# 03-GPS.net
KiCad netlist of a schematic drawn in Altium Designer
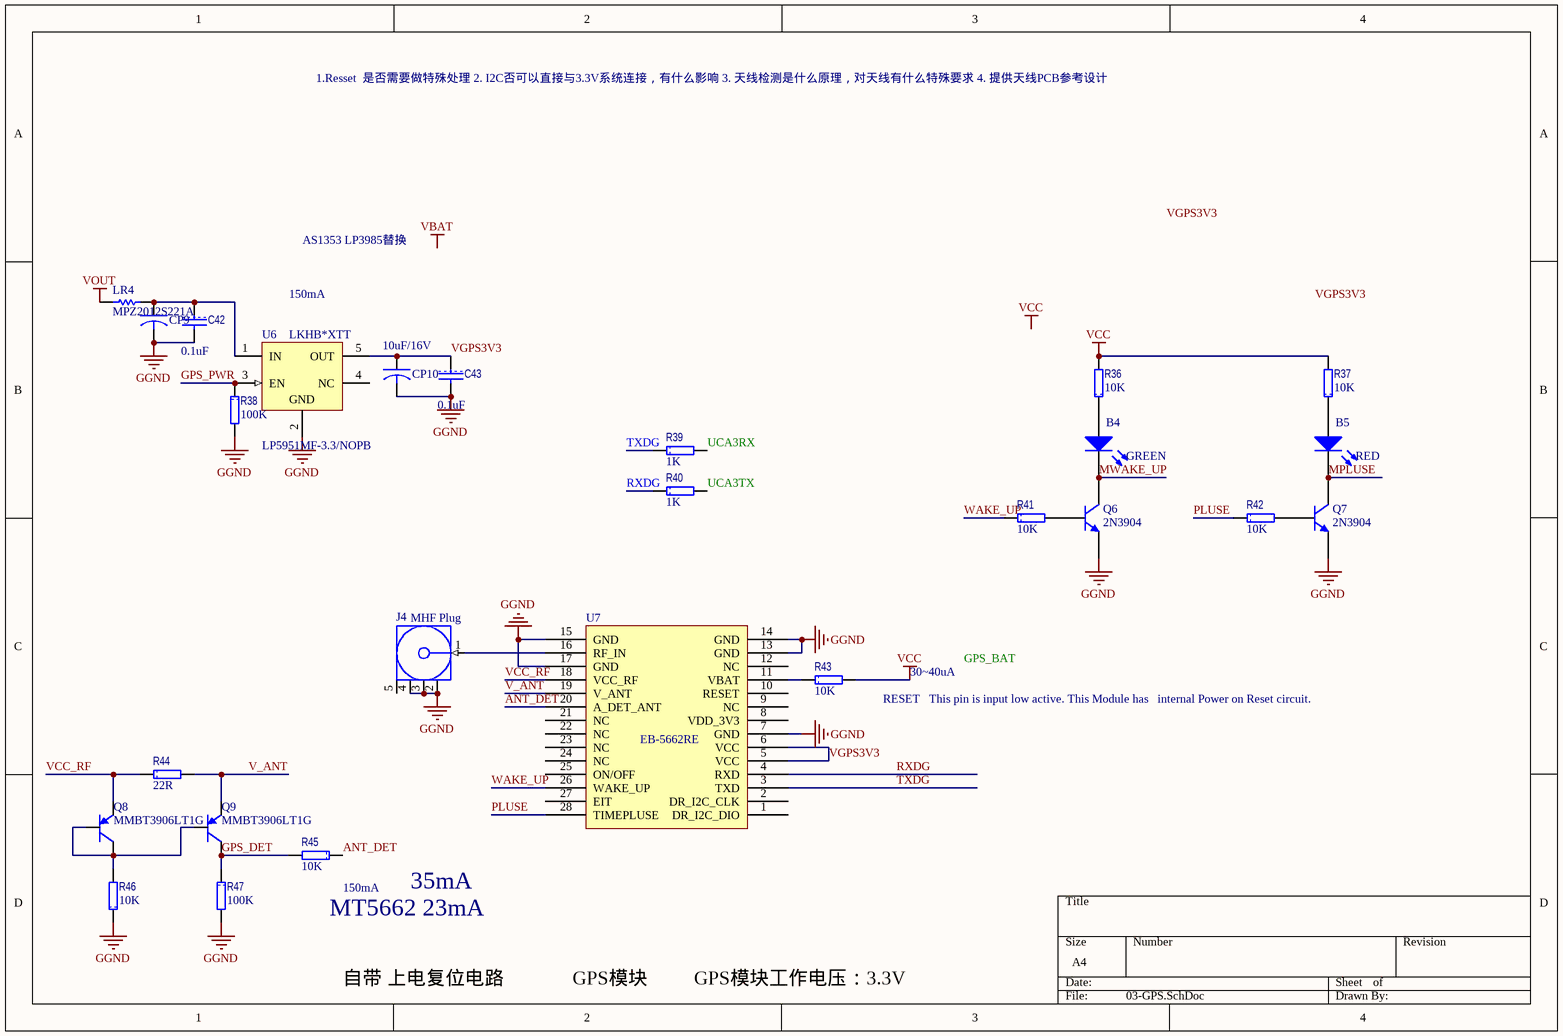
[diagram p0: 03-GPS.SchDoc]

(export (version "E")
  (design (tool "Eeschema 10.0.6"))
  (components
    (comp (ref "B4")
      (value "GREEN")
      (footprint "0805LED")
      (description "Typical RED, GREEN, YELLOW, AMBER GaAs LED")
      (fields (field (name "PUBLISHER") "Altium Limited"))
      (libsource (lib "Miscellaneous Devices") (part "LED2"))
    )
    (comp (ref "B5")
      (value "RED")
      (footprint "0805LED")
      (description "Typical RED, GREEN, YELLOW, AMBER GaAs LED")
      (fields (field (name "PUBLISHER") "Altium Limited"))
      (libsource (lib "Miscellaneous Devices") (part "LED2"))
    )
    (comp (ref "C42")
      (value "0.1uF")
      (footprint "1608[0603]C")
      (description "多层陶瓷电容器MLCC - SMD/SMT 0603 0.1uF 50volts X7R 10%")
      (fields (field (name "MANUFACTURER") "TDK") (field (name "MANUFACTURER PART NUMBER") "C1608X7R1H104K"))
      (libsource (lib "*") (part "CAP"))
    )
    (comp (ref "C43")
      (value "0.1uF")
      (footprint "1608[0603]C")
      (description "多层陶瓷电容器MLCC - SMD/SMT 0603 0.1uF 50volts X7R 10%")
      (fields (field (name "MANUFACTURER") "TDK") (field (name "MANUFACTURER PART NUMBER") "C1608X7R1H104K"))
      (libsource (lib "*") (part "CAP"))
    )
    (comp (ref "CP9")
      (value "TAJA106K016RNJ")
      (footprint "3216[1206]CB")
      (description "钽质电容器-固体SMD 16volts 10uF 10%")
      (fields (field (name "MANUFACTURER") "AVX"))
      (libsource (lib "*") (part "CAPACITOR"))
    )
    (comp (ref "CP10")
      (value "10uF/16V")
      (footprint "3216[1206]CB")
      (description "钽质电容器-固体SMD 16volts 10uF 10%")
      (fields (field (name "MANUFACTURER") "AVX") (field (name "MANUFACTURER PART NUMBER") "TAJA106K016RNJ"))
      (libsource (lib "*") (part "CAPACITOR"))
    )
    (comp (ref "J4")
      (value "MHF Plug")
      (footprint "MHF[MCB3]-V4")
      (description "插针 RF 连接器 ONBRD IPEX MHF RECEPTACLE")
      (fields
        (field (name "MANUFACTURER") "Taoglas")
        (field (name "MANUFACTURER PART NUMBER") "RECE-20279-001E-01")
      )
      (libsource (lib "Miscellaneous Connectors") (part "COAX-F"))
    )
    (comp (ref "LR4")
      (value "MPZ2012S221A")
      (footprint "2012[0805]")
      (description "电磁干扰滤波珠子、扼流圈和阵列 Ferrite Chip Beads")
      (fields (field (name "MANUFACTURER") "TDK"))
      (libsource (lib "Miscellaneous Devices") (part "Res Semi"))
    )
    (comp (ref "Q6")
      (value "2N3904")
      (footprint "SOT23_N")
      (description "NPN General Purpose Amplifier")
      (fields (field (name "PUBLISHER") "Altium Limited"))
      (libsource (lib "Miscellaneous Devices") (part "2N3904"))
    )
    (comp (ref "Q7")
      (value "2N3904")
      (footprint "SOT23_N")
      (description "NPN General Purpose Amplifier")
      (fields (field (name "PUBLISHER") "Altium Limited"))
      (libsource (lib "Miscellaneous Devices") (part "2N3904"))
    )
    (comp (ref "Q8")
      (value "MMBT3906LT1G")
      (footprint "SOT23_N")
      (description "两极晶体管 - BJT 200mA 40V PNP")
      (fields (field (name "MANUFACTURER") "ON Semiconductor"))
      (libsource (lib "*") (part "MMBT3096"))
    )
    (comp (ref "Q9")
      (value "MMBT3906LT1G")
      (footprint "SOT23_N")
      (description "两极晶体管 - BJT 200mA 40V PNP")
      (fields (field (name "MANUFACTURER") "ON Semiconductor"))
      (libsource (lib "*") (part "MMBT3096"))
    )
    (comp (ref "R36")
      (value "10K")
      (footprint "1608[0603]R")
      (description "厚膜电阻器 - SMD 1/10watt 10Kohms 1%")
      (fields
        (field (name "MANUFACTURER") "Vishay / Dale")
        (field (name "MANUFACTURER PART NUMBER") "CRCW060310K0FKEA")
      )
      (libsource (lib "10K 1%") (part "RES"))
    )
    (comp (ref "R37")
      (value "10K")
      (footprint "1608[0603]R")
      (description "厚膜电阻器 - SMD 1/10watt 10Kohms 1%")
      (fields
        (field (name "MANUFACTURER") "Vishay / Dale")
        (field (name "MANUFACTURER PART NUMBER") "CRCW060310K0FKEA")
      )
      (libsource (lib "10K 1%") (part "RES"))
    )
    (comp (ref "R38")
      (value "100K")
      (footprint "1608[0603]R")
      (description "厚膜电阻器 - SMD 1/10watt 100Kohms 1%")
      (fields
        (field (name "MANUFACTURER") "Vishay / Dale")
        (field (name "MANUFACTURER PART NUMBER") "CRCW0603100KFKEA")
      )
      (libsource (lib "100K 1%") (part "RES"))
    )
    (comp (ref "R39")
      (value "1K")
      (footprint "1608[0603]R")
      (description "厚膜电阻器 - SMD 1/10watt 1.0Kohms 1%")
      (fields
        (field (name "MANUFACTURER") "Vishay / Dale")
        (field (name "MANUFACTURER PART NUMBER") "CRCW06031K00FKEA")
      )
      (libsource (lib "1K 1%") (part "RES"))
    )
    (comp (ref "R40")
      (value "1K")
      (footprint "1608[0603]R")
      (description "厚膜电阻器 - SMD 1/10watt 1.0Kohms 1%")
      (fields
        (field (name "MANUFACTURER") "Vishay / Dale")
        (field (name "MANUFACTURER PART NUMBER") "CRCW06031K00FKEA")
      )
      (libsource (lib "1K 1%") (part "RES"))
    )
    (comp (ref "R41")
      (value "10K")
      (footprint "1608[0603]R")
      (description "厚膜电阻器 - SMD 1/10watt 10Kohms 1%")
      (fields
        (field (name "MANUFACTURER") "Vishay / Dale")
        (field (name "MANUFACTURER PART NUMBER") "CRCW060310K0FKEA")
      )
      (libsource (lib "10K 1%") (part "RES"))
    )
    (comp (ref "R42")
      (value "10K")
      (footprint "1608[0603]R")
      (description "厚膜电阻器 - SMD 1/10watt 10Kohms 1%")
      (fields
        (field (name "MANUFACTURER") "Vishay / Dale")
        (field (name "MANUFACTURER PART NUMBER") "CRCW060310K0FKEA")
      )
      (libsource (lib "10K 1%") (part "RES"))
    )
    (comp (ref "R43")
      (value "10K")
      (footprint "1608[0603]R")
      (description "厚膜电阻器 - SMD 1/10watt 10Kohms 1%")
      (fields
        (field (name "MANUFACTURER") "Vishay / Dale")
        (field (name "MANUFACTURER PART NUMBER") "CRCW060310K0FKEA")
      )
      (libsource (lib "10K 1%") (part "RES"))
    )
    (comp (ref "R44")
      (value "22R")
      (footprint "1608[0603]R")
      (description "厚膜电阻器 - SMD 1/10watt 22ohms 1%")
      (fields
        (field (name "MANUFACTURER") "Vishay / Dale")
        (field (name "MANUFACTURER PART NUMBER") "CRCW060322R0FKEA")
      )
      (libsource (lib "22R 1%") (part "RES"))
    )
    (comp (ref "R45")
      (value "10K")
      (footprint "1608[0603]R")
      (description "厚膜电阻器 - SMD 1/10watt 10Kohms 1%")
      (fields
        (field (name "MANUFACTURER") "Vishay / Dale")
        (field (name "MANUFACTURER PART NUMBER") "CRCW060310K0FKEA")
      )
      (libsource (lib "10K 1%") (part "RES"))
    )
    (comp (ref "R46")
      (value "10K")
      (footprint "1608[0603]R")
      (description "厚膜电阻器 - SMD 1/10watt 10Kohms 1%")
      (fields
        (field (name "MANUFACTURER") "Vishay / Dale")
        (field (name "MANUFACTURER PART NUMBER") "CRCW060310K0FKEA")
      )
      (libsource (lib "10K 1%") (part "RES"))
    )
    (comp (ref "R47")
      (value "100K")
      (footprint "1608[0603]R")
      (description "厚膜电阻器 - SMD 1/10watt 100Kohms 1%")
      (fields
        (field (name "MANUFACTURER") "Vishay / Dale")
        (field (name "MANUFACTURER PART NUMBER") "CRCW0603100KFKEA")
      )
      (libsource (lib "100K 1%") (part "RES"))
    )
    (comp (ref "U6")
      (value "LP5951MF-3.3/NOPB")
      (footprint "MF05A_N")
      (description "Micropower, 150mA Low-Dropout CMOS Voltage Regulator, 5-pin SOT-23, Pb-Free")
      (fields
        (field (name "PACKAGETOPMARKING") "LKHB*XTT")
        (field (name "MANUFACTURER") "National Semiconductor")
        (field (name "PUBLISHER") "Altium Limited")
      )
      (libsource (lib "NSC LDO") (part "LP5951MF-3.3/NOPB"))
    )
    (comp (ref "U7")
      (value "EB-5662RE")
      (footprint "EB-5662RE")
      (description "GPS模块")
      (libsource (lib "*") (part "EB-5662RE"))
    )
  )
  (nets
    (net (code "1") (name "/ANT_DET") (class "Default")
      (node (ref "R45") (pin "1") (pinfunction "1_1") (pintype "passive"))
      (node (ref "U7") (pin "20") (pinfunction "A_DET_ANT_20") (pintype "passive"))
    )
    (net (code "3") (name "/GPS_DET") (class "Default")
      (node (ref "Q9") (pin "3") (pinfunction "3_3") (pintype "passive"))
      (node (ref "R45") (pin "2") (pinfunction "2_2") (pintype "passive"))
      (node (ref "R47") (pin "1") (pinfunction "1_1") (pintype "passive"))
    )
    (net (code "4") (name "/GPS_PWR") (class "Default")
      (node (ref "R38") (pin "1") (pinfunction "1_1") (pintype "passive"))
      (node (ref "U6") (pin "3") (pinfunction "EN_3") (pintype "input"))
    )
    (net (code "5") (name "/MPLUSE") (class "Default")
      (node (ref "B5") (pin "2") (pinfunction "K_2") (pintype "passive"))
      (node (ref "Q7") (pin "3") (pinfunction "C_3") (pintype "passive"))
    )
    (net (code "6") (name "/MWAKE_UP") (class "Default")
      (node (ref "B4") (pin "2") (pinfunction "K_2") (pintype "passive"))
      (node (ref "Q6") (pin "3") (pinfunction "C_3") (pintype "passive"))
    )
    (net (code "7") (name "/PLUSE") (class "Default")
      (node (ref "R42") (pin "1") (pinfunction "1_1") (pintype "passive"))
      (node (ref "U7") (pin "28") (pinfunction "TIMEPLUSE_28") (pintype "passive"))
    )
    (net (code "8") (name "/RXDG") (class "Default")
      (node (ref "R40") (pin "1") (pinfunction "1_1") (pintype "passive"))
      (node (ref "U7") (pin "4") (pinfunction "RXD_4") (pintype "passive"))
    )
    (net (code "9") (name "/TXDG") (class "Default")
      (node (ref "R39") (pin "1") (pinfunction "1_1") (pintype "passive"))
      (node (ref "U7") (pin "3") (pinfunction "TXD_3") (pintype "passive"))
    )
    (net (code "10") (name "/UCA3RX") (class "Default")
      (node (ref "R39") (pin "2") (pinfunction "2_2") (pintype "passive"))
    )
    (net (code "11") (name "/UCA3TX") (class "Default")
      (node (ref "R40") (pin "2") (pinfunction "2_2") (pintype "passive"))
    )
    (net (code "12") (name "/VCC_RF") (class "Default")
      (node (ref "Q8") (pin "2") (pinfunction "2_2") (pintype "passive"))
      (node (ref "R44") (pin "1") (pinfunction "1_1") (pintype "passive"))
      (node (ref "U7") (pin "18") (pinfunction "VCC_RF_18") (pintype "passive"))
    )
    (net (code "13") (name "/VGPS3V3") (class "Default")
      (node (ref "C43") (pin "1") (pinfunction "1_1") (pintype "passive"))
      (node (ref "CP10") (pin "1") (pinfunction "1_1") (pintype "passive"))
      (node (ref "U6") (pin "5") (pinfunction "OUT_5") (pintype "power_in"))
      (node (ref "U7") (pin "5") (pinfunction "VCC_5") (pintype "passive"))
      (node (ref "U7") (pin "6") (pinfunction "VCC_6") (pintype "passive"))
    )
    (net (code "14") (name "/V_ANT") (class "Default")
      (node (ref "Q9") (pin "2") (pinfunction "2_2") (pintype "passive"))
      (node (ref "R44") (pin "2") (pinfunction "2_2") (pintype "passive"))
      (node (ref "U7") (pin "19") (pinfunction "V_ANT_19") (pintype "passive"))
    )
    (net (code "15") (name "/WAKE_UP") (class "Default")
      (node (ref "R41") (pin "1") (pinfunction "1_1") (pintype "passive"))
      (node (ref "U7") (pin "26") (pinfunction "WAKE_UP_26") (pintype "passive"))
    )
    (net (code "16") (name "GGND") (class "Default")
      (node (ref "C42") (pin "2") (pinfunction "2_2") (pintype "passive"))
      (node (ref "C43") (pin "2") (pinfunction "2_2") (pintype "passive"))
      (node (ref "CP10") (pin "2") (pinfunction "2_2") (pintype "passive"))
      (node (ref "CP9") (pin "2") (pinfunction "2_2") (pintype "passive"))
      (node (ref "J4") (pin "2") (pinfunction "GND_2") (pintype "power_in"))
      (node (ref "J4") (pin "3") (pinfunction "GND_3") (pintype "power_in"))
      (node (ref "J4") (pin "4") (pinfunction "GND_4") (pintype "power_in"))
      (node (ref "Q6") (pin "1") (pinfunction "E_1") (pintype "passive"))
      (node (ref "Q7") (pin "1") (pinfunction "E_1") (pintype "passive"))
      (node (ref "R38") (pin "2") (pinfunction "2_2") (pintype "passive"))
      (node (ref "R46") (pin "1") (pinfunction "1_1") (pintype "passive"))
      (node (ref "R47") (pin "2") (pinfunction "2_2") (pintype "passive"))
      (node (ref "U6") (pin "2") (pinfunction "GND_2") (pintype "power_in"))
      (node (ref "U7") (pin "13") (pinfunction "GND_13") (pintype "passive"))
      (node (ref "U7") (pin "14") (pinfunction "GND_14") (pintype "passive"))
      (node (ref "U7") (pin "15") (pinfunction "GND_15") (pintype "passive"))
      (node (ref "U7") (pin "17") (pinfunction "GND_17") (pintype "passive"))
      (node (ref "U7") (pin "7") (pinfunction "GND_7") (pintype "passive"))
    )
    (net (code "17") (name "Net-(B4-A)") (class "Default")
      (node (ref "B4") (pin "1") (pinfunction "A_1") (pintype "passive"))
      (node (ref "R36") (pin "1") (pinfunction "1_1") (pintype "passive"))
    )
    (net (code "18") (name "Net-(B5-A)") (class "Default")
      (node (ref "B5") (pin "1") (pinfunction "A_1") (pintype "passive"))
      (node (ref "R37") (pin "1") (pinfunction "1_1") (pintype "passive"))
    )
    (net (code "19") (name "Net-(J4-Signal)") (class "Default")
      (node (ref "J4") (pin "1") (pinfunction "Signal_1") (pintype "input"))
      (node (ref "U7") (pin "16") (pinfunction "RF_IN_16") (pintype "passive"))
    )
    (net (code "20") (name "Net-(Q6-B)") (class "Default")
      (node (ref "Q6") (pin "2") (pinfunction "B_2") (pintype "passive"))
      (node (ref "R41") (pin "2") (pinfunction "2_2") (pintype "passive"))
    )
    (net (code "21") (name "Net-(Q7-B)") (class "Default")
      (node (ref "Q7") (pin "2") (pinfunction "B_2") (pintype "passive"))
      (node (ref "R42") (pin "2") (pinfunction "2_2") (pintype "passive"))
    )
    (net (code "22") (name "Net-(Q8-Pad1)") (class "Default")
      (node (ref "Q8") (pin "1") (pinfunction "1_1") (pintype "passive"))
      (node (ref "Q8") (pin "3") (pinfunction "3_3") (pintype "passive"))
      (node (ref "Q9") (pin "1") (pinfunction "1_1") (pintype "passive"))
      (node (ref "R46") (pin "2") (pinfunction "2_2") (pintype "passive"))
    )
    (net (code "23") (name "Net-(U6-IN)") (class "Default")
      (node (ref "C42") (pin "1") (pinfunction "1_1") (pintype "passive"))
      (node (ref "CP9") (pin "1") (pinfunction "1_1") (pintype "passive"))
      (node (ref "LR4") (pin "2") (pinfunction "2_2") (pintype "passive"))
      (node (ref "U6") (pin "1") (pinfunction "IN_1") (pintype "power_in"))
    )
    (net (code "24") (name "Net-(U7-VBAT)") (class "Default")
      (node (ref "R43") (pin "1") (pinfunction "1_1") (pintype "passive"))
      (node (ref "U7") (pin "11") (pinfunction "VBAT_11") (pintype "passive"))
    )
    (net (code "26") (name "VCC") (class "Default")
      (node (ref "R36") (pin "2") (pinfunction "2_2") (pintype "passive"))
      (node (ref "R37") (pin "2") (pinfunction "2_2") (pintype "passive"))
      (node (ref "R43") (pin "2") (pinfunction "2_2") (pintype "passive"))
    )
    (net (code "27") (name "VOUT") (class "Default")
      (node (ref "LR4") (pin "1") (pinfunction "1_1") (pintype "passive"))
    )
    (net (code "28") (name "unconnected-(J4-GND-Pad5)") (class "Default")
      (node (ref "J4") (pin "5") (pinfunction "GND_5") (pintype "power_in"))
    )
    (net (code "29") (name "unconnected-(U6-NC-Pad4)") (class "Default")
      (node (ref "U6") (pin "4") (pinfunction "NC_4") (pintype "passive"))
    )
    (net (code "30") (name "unconnected-(U7-DR_I2C_CLK-Pad2)") (class "Default")
      (node (ref "U7") (pin "2") (pinfunction "DR_I2C_CLK_2") (pintype "passive"))
    )
    (net (code "31") (name "unconnected-(U7-DR_I2C_DIO-Pad1)") (class "Default")
      (node (ref "U7") (pin "1") (pinfunction "DR_I2C_DIO_1") (pintype "passive"))
    )
    (net (code "32") (name "unconnected-(U7-EIT-Pad27)") (class "Default")
      (node (ref "U7") (pin "27") (pinfunction "EIT_27") (pintype "passive"))
    )
    (net (code "33") (name "unconnected-(U7-NC-Pad9)") (class "Default")
      (node (ref "U7") (pin "9") (pinfunction "NC_9") (pintype "passive"))
    )
    (net (code "34") (name "unconnected-(U7-NC-Pad12)") (class "Default")
      (node (ref "U7") (pin "12") (pinfunction "NC_12") (pintype "passive"))
    )
    (net (code "35") (name "unconnected-(U7-NC-Pad21)") (class "Default")
      (node (ref "U7") (pin "21") (pinfunction "NC_21") (pintype "passive"))
    )
    (net (code "36") (name "unconnected-(U7-NC-Pad22)") (class "Default")
      (node (ref "U7") (pin "22") (pinfunction "NC_22") (pintype "passive"))
    )
    (net (code "37") (name "unconnected-(U7-NC-Pad23)") (class "Default")
      (node (ref "U7") (pin "23") (pinfunction "NC_23") (pintype "passive"))
    )
    (net (code "38") (name "unconnected-(U7-NC-Pad24)") (class "Default")
      (node (ref "U7") (pin "24") (pinfunction "NC_24") (pintype "passive"))
    )
    (net (code "39") (name "unconnected-(U7-ON{slash}OFF-Pad25)") (class "Default")
      (node (ref "U7") (pin "25") (pinfunction "ON/OFF_25") (pintype "passive"))
    )
    (net (code "40") (name "unconnected-(U7-RESET-Pad10)") (class "Default")
      (node (ref "U7") (pin "10") (pinfunction "RESET_10") (pintype "passive"))
    )
    (net (code "41") (name "unconnected-(U7-VDD_3V3-Pad8)") (class "Default")
      (node (ref "U7") (pin "8") (pinfunction "VDD_3V3_8") (pintype "passive"))
    )
  )
)
